# CAN_USB_DISPLAY.net
KiCad netlist of a schematic drawn in Altium Designer
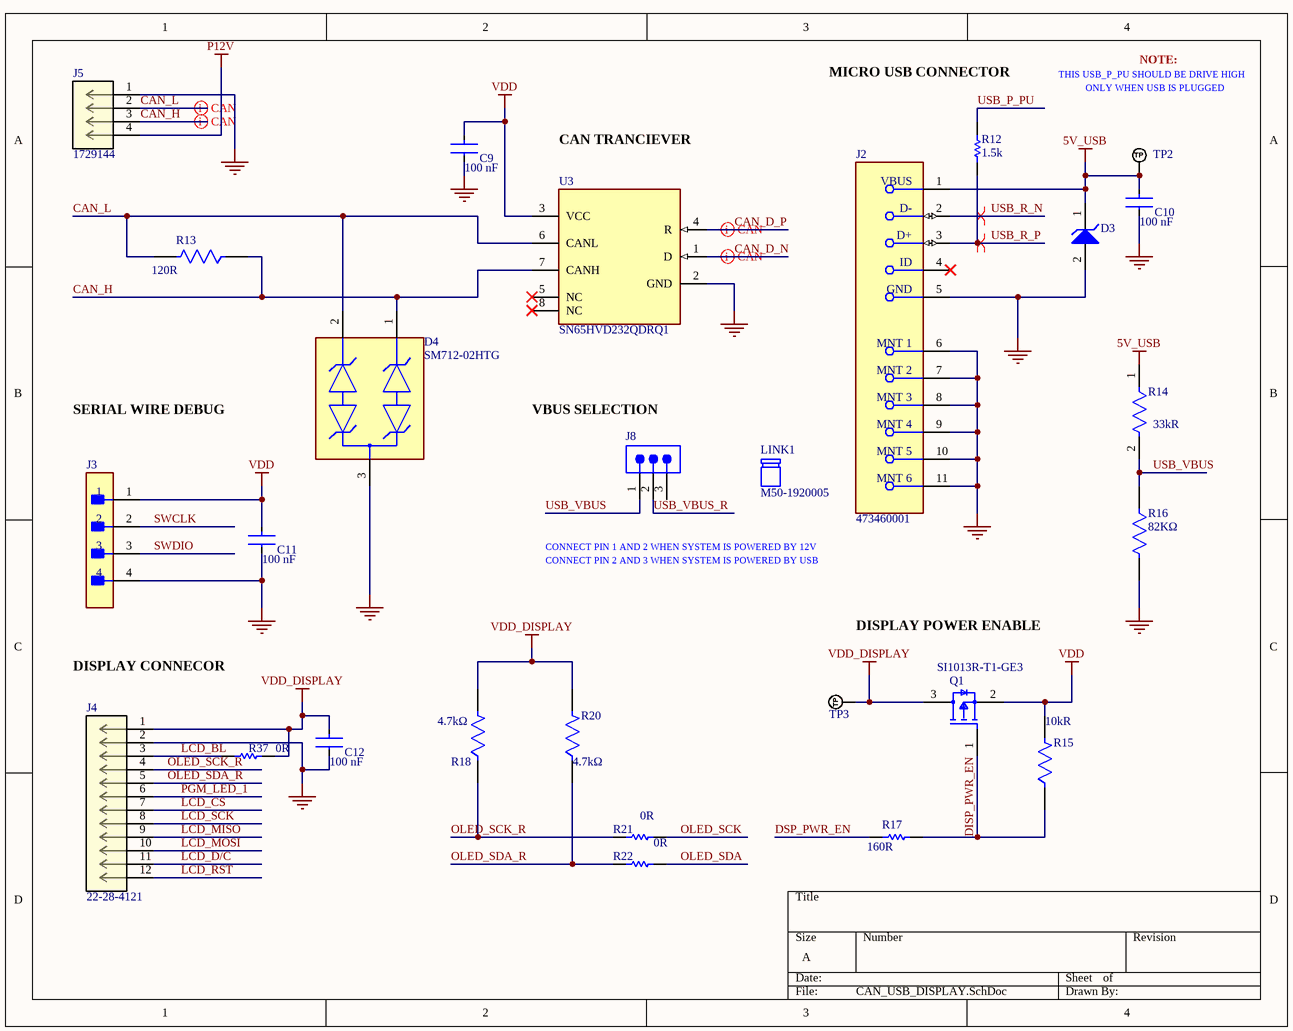
[diagram p0: CAN_USB_DISPLAY.SchDoc]

(export (version "E")
  (design (tool "Eeschema 10.0.6"))
  (components
    (comp (ref "C9")
      (value "CC0402KRX7R7BB104")
      (footprint "FP-CC0402-MFG")
      (description "CAP CER 0.1UF 16V X7R 0402")
      (fields
        (field (name "CAPACITANCE") "100 nF")
        (field (name "MANUFACTURER") "YAGEO")
        (field (name "TOLERANCE") "0.1")
      )
      (libsource (lib "Altium Content Vault") (part "11868f565c42a9108669ba33697ecf6"))
    )
    (comp (ref "C10")
      (value "CC0402KRX7R7BB104")
      (footprint "FP-CC0402-MFG")
      (description "CAP CER 0.1UF 16V X7R 0402")
      (fields
        (field (name "CAPACITANCE") "100 nF")
        (field (name "MANUFACTURER") "YAGEO")
        (field (name "TOLERANCE") "0.1")
      )
      (libsource (lib "Altium Content Vault") (part "11868f565c42a9108669ba33697ecf6"))
    )
    (comp (ref "C11")
      (value "CC0402KRX7R7BB104")
      (footprint "FP-CC0402-MFG")
      (description "CAP CER 0.1UF 16V X7R 0402")
      (fields
        (field (name "CAPACITANCE") "100 nF")
        (field (name "MANUFACTURER") "YAGEO")
        (field (name "TOLERANCE") "0.1")
      )
      (libsource (lib "Altium Content Vault") (part "11868f565c42a9108669ba33697ecf6"))
    )
    (comp (ref "C12")
      (value "CC0402KRX7R7BB104")
      (footprint "FP-CC0402-MFG")
      (description "CAP CER 0.1UF 16V X7R 0402")
      (fields
        (field (name "CAPACITANCE") "100 nF")
        (field (name "MANUFACTURER") "YAGEO")
        (field (name "TOLERANCE") "0.1")
      )
      (libsource (lib "Altium Content Vault") (part "11868f565c42a9108669ba33697ecf6"))
    )
    (comp (ref "D3")
      (value "ESD5Z5.0T1G")
      (footprint "ONSC-SOD-523-2-502-01_V")
      (fields (field (name "MANUFACTURER") "On Semiconductor"))
      (libsource (lib "Altium Content Vault") (part "ONSC-K1A2-2"))
    )
    (comp (ref "D4")
      (value "SM712-02HTG")
      (footprint "FP-SM712-MFG")
      (description "TVS DIODE 12V 31V SOT23-3")
      (libsource (lib "Altium Content Vault") (part "30adef48d791aa94530531f6d7a3f92"))
    )
    (comp (ref "J2")
      (value "473460001")
      (footprint "FP-473460001-MFG")
      (description "CONN RCPT USB2.0 MICRO B SMD R/A")
      (fields
        (field (name "OCTOPART") "https://octopart.com/47346-0001-molex-7164928")
        (field (name "MANUFACTURER") "Molex")
      )
      (libsource (lib "Altium Content Vault") (part "53ae1f1d9b557310b43ca686e5bb76a"))
    )
    (comp (ref "J3")
      (value "HTSW-104-07-G-S")
      (footprint "FP-HTSW-104-07-G-S-MFG")
      (description "CONN HEADER VERT 4POS 2.54MM")
      (libsource (lib "Altium Content Vault") (part "299a8cea1bdcbc3624fe62c390fa72c"))
    )
    (comp (ref "J4")
      (value "22-28-4121")
      (footprint "12 POS_2.54MM_MOLEX")
      (description "KK 254 Breakaway Header, Vertical, 12 Circuits, Tin (Sn) Plating, Mating Pin Length 8.13mm")
      (fields (field (name "MANUFACTURER") "Molex"))
      (libsource (lib "F1_MODULE") (part "22-28-4121"))
    )
    (comp (ref "J5")
      (value "1729144")
      (footprint "PHOENIX_1729144")
      (description "Block, Terminal; 13.5 A; 250 V; 5.08 mm; 26 to 16 AWG; 4; Screw; Solder; 4 kV")
      (fields (field (name "MANUFACTURER") "Phoenix Contact") (field (name "VOLTAGE") "300V"))
      (libsource (lib "F1_MODULE") (part "1729144"))
    )
    (comp (ref "J8")
      (value "61300311121")
      (footprint "61300311121")
      (description "CONN HEADER VERT 3POS 2.54MM")
      (libsource (lib "Altium Content Vault") (part "Header_Male_1R_03P"))
    )
    (comp (ref "LINK1")
      (value "M50-1920005")
      (description "CONN SHUNT 1.27MM RED")
      (fields (field (name "MANUFACTURER") "Harwin") (field (name "LCSC PART NUMBER") "C6985646"))
      (libsource (lib "Schlib") (part "M50-1920005"))
    )
    (comp (ref "Q1")
      (value "SI1013R-T1-GE3")
      (footprint "FP-C15-1445-MFG")
      (description "MOSFET P-CH 20V 350MA SC75A")
      (libsource (lib "Altium Content Vault") (part "274ba75a4227b453460520a6808ef61"))
    )
    (comp (ref "R12")
      (value "ERA2AEB152X")
      (footprint "RESC1005X40X25LL10T10")
      (description "RES SMD 1.5K OHM 0.1% 1/16W 0402")
      (fields (field (name "MANUFACTURER") "Panasonic") (field (name "RESISTANCE") "1.5k"))
      (libsource (lib "Altium Content Vault") (part "RES"))
    )
    (comp (ref "R13")
      (value "RMCF1206FTR120")
      (footprint "FP-RMCF1206-MFG")
      (description "0.12Ω ±1% 0.25W 1206 Thick Film Chip Resistor AEC-Q200 compliant")
      (fields (field (name "TOLERANCE") "1%") (field (name "RESISTANCE") "120R"))
      (libsource (lib "Altium Content Vault") (part "1029c3af85768c4190bb7ad29bc67b5"))
    )
    (comp (ref "R14")
      (value "ERA-2AEB333X")
      (footprint "FP-ERA2A-MFG")
      (description "RES SMD 33K OHM 0.1% 1/16W 0402")
      (fields (field (name "TOLERANCE") "0.1%") (field (name "RESISTANCE") "33kR"))
      (libsource (lib "") (part "1029c3af85768c4190bb7ad29bc67b5_1"))
    )
    (comp (ref "R15")
      (value "RC0402JR-0710KL")
      (footprint "FP-RC0402-0_4-MFG")
      (description "RES 10K OHM 5% 1/16W 0402")
      (fields (field (name "RESISTANCE") "10kR") (field (name "TOLERANCE") "5%"))
      (libsource (lib "Altium Content Vault") (part "1029c3af85768c4190bb7ad29bc67b5"))
    )
    (comp (ref "R16")
      (value "CRGCQ0402F82K")
      (footprint "FP-CRGCQ0402-IPC_C")
      (description "CRGCQ0402 82KΩ 1% ±100ppm/°C 50V")
      (fields
        (field (name "MANUFACTURER") "TE Connectivity")
        (field (name "OCTOPART") "https://octopart.com/crgcq0402f82k-te+connectivity-91017988")
        (field (name "RESISTANCE") "82KΩ")
      )
      (libsource (lib "Altium Content Vault") (part "1029c3af85768c4190bb7ad29bc67b5"))
    )
    (comp (ref "R17")
      (value "ERJ-2GEJ161X")
      (footprint "RESC1005X40X25NL05T05")
      (fields (field (name "MANUFACTURER") "Panasonic") (field (name "RESISTANCE") "160R"))
      (libsource (lib "Altium Content Vault") (part "RES"))
    )
    (comp (ref "R18")
      (value "RC0402JR-074K7L")
      (footprint "FP-RC0402-0_4-MFG")
      (description "4.7 kOhms ±5% 0.063W, 1/16W Chip Resistor 0402 (1005 Metric) Moisture Resistant Thick Film")
      (fields (field (name "TOLERANCE") "5%") (field (name "RESISTANCE") "4.7kΩ"))
      (libsource (lib "Altium Content Vault") (part "RC0402JR-074K7L"))
    )
    (comp (ref "R20")
      (value "RC0402JR-074K7L")
      (footprint "FP-RC0402-0_4-MFG")
      (description "4.7 kOhms ±5% 0.063W, 1/16W Chip Resistor 0402 (1005 Metric) Moisture Resistant Thick Film")
      (fields (field (name "TOLERANCE") "5%") (field (name "RESISTANCE") "4.7kΩ"))
      (libsource (lib "Altium Content Vault") (part "RC0402JR-074K7L"))
    )
    (comp (ref "R21")
      (value "ERJ2GE0R00X")
      (footprint "RESC1005X40X25LL05T05")
      (description "Chip Resistor, 0 Ohm, 0.1 W, -55 to 155 degC, 0402 (1005 Metric), RoHS, Tape and Reel")
      (fields
        (field (name "MANUFACTURER") "Panasonic")
        (field (name "RESISTANCE") "0R")
        (field (name "TOLERANCE") "5%")
      )
      (libsource (lib "Altium Content Vault") (part "RES-2"))
    )
    (comp (ref "R22")
      (value "ERJ2GE0R00X")
      (footprint "RESC1005X40X25LL05T05")
      (description "Chip Resistor, 0 Ohm, 0.1 W, -55 to 155 degC, 0402 (1005 Metric), RoHS, Tape and Reel")
      (fields
        (field (name "MANUFACTURER") "Panasonic")
        (field (name "RESISTANCE") "0R")
        (field (name "TOLERANCE") "5%")
      )
      (libsource (lib "Altium Content Vault") (part "RES-2"))
    )
    (comp (ref "R37")
      (value "ERJ2GE0R00X")
      (footprint "RESC1005X40X25LL05T05")
      (description "Chip Resistor, 0 Ohm, 0.1 W, -55 to 155 degC, 0402 (1005 Metric), RoHS, Tape and Reel")
      (fields
        (field (name "MANUFACTURER") "Panasonic")
        (field (name "RESISTANCE") "0R")
        (field (name "TOLERANCE") "5%")
      )
      (libsource (lib "Altium Content Vault") (part "RES-2"))
    )
    (comp (ref "TP2")
      (value "TP_NOBOM")
      (footprint "PAD_RND_1MM")
      (description "Test Point Round 1mm (NO BOM)")
      (libsource (lib "Schematic-Lib-PhilsLab") (part "TEST_POINT_RND_1MM"))
    )
    (comp (ref "TP3")
      (value "TP_NOBOM")
      (footprint "PAD_RND_1MM")
      (description "Test Point Round 1mm (NO BOM)")
      (libsource (lib "Schematic-Lib-PhilsLab") (part "TEST_POINT_RND_1MM"))
    )
    (comp (ref "U3")
      (value "SN65HVD232QDRQ1")
      (footprint "CAN IC")
      (description "Texas Instruments - SN65HVD232QDRQ1 - Can Bus, Transceiver, Can, 1, 1, 3 V, 3.6 V, SOIC")
      (fields (field (name "MANUFACTURER") "Texas Instruments"))
      (libsource (lib "F1_MODULE") (part "SN65HVD232QDRQ1"))
    )
  )
  (nets
    (net (code "1") (name "/CAN_D_N") (class "Default")
      (node (ref "U3") (pin "1") (pinfunction "D_1") (pintype "input"))
    )
    (net (code "2") (name "/CAN_D_P") (class "Default")
      (node (ref "U3") (pin "4") (pinfunction "R_4") (pintype "input"))
    )
    (net (code "3") (name "/CAN_H") (class "Default")
      (node (ref "D4") (pin "1") (pinfunction "1_1") (pintype "passive"))
      (node (ref "J5") (pin "3") (pinfunction "3_3") (pintype "passive"))
      (node (ref "R13") (pin "1") (pinfunction "1_1") (pintype "passive"))
      (node (ref "U3") (pin "7") (pinfunction "CANH_7") (pintype "passive"))
    )
    (net (code "4") (name "/CAN_L") (class "Default")
      (node (ref "D4") (pin "2") (pinfunction "2_2") (pintype "passive"))
      (node (ref "J5") (pin "2") (pinfunction "2_2") (pintype "passive"))
      (node (ref "R13") (pin "2") (pinfunction "2_2") (pintype "passive"))
      (node (ref "U3") (pin "6") (pinfunction "CANL_6") (pintype "passive"))
    )
    (net (code "5") (name "/DISP_PWR_EN") (class "Default")
      (node (ref "Q1") (pin "1") (pinfunction "G_1") (pintype "passive"))
      (node (ref "R15") (pin "1") (pinfunction "1_1") (pintype "passive"))
      (node (ref "R17") (pin "2") (pinfunction "2_2") (pintype "passive"))
    )
    (net (code "6") (name "/DSP_PWR_EN") (class "Default")
      (node (ref "R17") (pin "1") (pinfunction "1_1") (pintype "passive"))
    )
    (net (code "7") (name "/LCD_BL") (class "Default")
      (node (ref "J4") (pin "3") (pinfunction "3_3") (pintype "passive"))
      (node (ref "R37") (pin "1") (pinfunction "1_1") (pintype "passive"))
    )
    (net (code "8") (name "/LCD_CS") (class "Default")
      (node (ref "J4") (pin "7") (pinfunction "7_7") (pintype "passive"))
    )
    (net (code "9") (name "/LCD_D{slash}C") (class "Default")
      (node (ref "J4") (pin "11") (pinfunction "11_11") (pintype "passive"))
    )
    (net (code "10") (name "/LCD_MISO") (class "Default")
      (node (ref "J4") (pin "9") (pinfunction "9_9") (pintype "passive"))
    )
    (net (code "11") (name "/LCD_MOSI") (class "Default")
      (node (ref "J4") (pin "10") (pinfunction "10_10") (pintype "passive"))
    )
    (net (code "12") (name "/LCD_RST") (class "Default")
      (node (ref "J4") (pin "12") (pinfunction "12_12") (pintype "passive"))
    )
    (net (code "13") (name "/LCD_SCK") (class "Default")
      (node (ref "J4") (pin "8") (pinfunction "8_8") (pintype "passive"))
    )
    (net (code "14") (name "/OLED_SCK") (class "Default")
      (node (ref "R21") (pin "2") (pinfunction "2_2") (pintype "passive"))
    )
    (net (code "15") (name "/OLED_SCK_R") (class "Default")
      (node (ref "J4") (pin "4") (pinfunction "4_4") (pintype "passive"))
      (node (ref "R18") (pin "1") (pinfunction "1_1") (pintype "passive"))
      (node (ref "R21") (pin "1") (pinfunction "1_1") (pintype "passive"))
    )
    (net (code "16") (name "/OLED_SDA") (class "Default")
      (node (ref "R22") (pin "2") (pinfunction "2_2") (pintype "passive"))
    )
    (net (code "17") (name "/OLED_SDA_R") (class "Default")
      (node (ref "J4") (pin "5") (pinfunction "5_5") (pintype "passive"))
      (node (ref "R20") (pin "1") (pinfunction "1_1") (pintype "passive"))
      (node (ref "R22") (pin "1") (pinfunction "1_1") (pintype "passive"))
    )
    (net (code "18") (name "/PGM_LED_1") (class "Default")
      (node (ref "J4") (pin "6") (pinfunction "6_6") (pintype "passive"))
    )
    (net (code "19") (name "/SWCLK") (class "Default")
      (node (ref "J3") (pin "2") (pinfunction "2_2") (pintype "passive"))
    )
    (net (code "20") (name "/SWDIO") (class "Default")
      (node (ref "J3") (pin "3") (pinfunction "3_3") (pintype "passive"))
    )
    (net (code "21") (name "/USB_P_PU") (class "Default")
      (node (ref "R12") (pin "2") (pinfunction "2_2") (pintype "passive"))
    )
    (net (code "22") (name "/USB_R_N") (class "Default")
      (node (ref "J2") (pin "2") (pinfunction "D-_2") (pintype "bidirectional"))
    )
    (net (code "23") (name "/USB_R_P") (class "Default")
      (node (ref "J2") (pin "3") (pinfunction "D+_3") (pintype "bidirectional"))
      (node (ref "R12") (pin "1") (pinfunction "1_1") (pintype "passive"))
    )
    (net (code "24") (name "/USB_VBUS") (class "Default")
      (node (ref "J8") (pin "1") (pinfunction "1_1") (pintype "passive"))
      (node (ref "R14") (pin "2") (pinfunction "2_2") (pintype "passive"))
      (node (ref "R16") (pin "1") (pinfunction "1_1") (pintype "passive"))
    )
    (net (code "25") (name "/USB_VBUS_R") (class "Default")
      (node (ref "J8") (pin "2") (pinfunction "2_2") (pintype "passive"))
    )
    (net (code "26") (name "5V_USB") (class "Default")
      (node (ref "C10") (pin "1") (pinfunction "1_1") (pintype "passive"))
      (node (ref "D3") (pin "1") (pinfunction "K_1") (pintype "passive"))
      (node (ref "J2") (pin "1") (pinfunction "VBUS_1") (pintype "power_in"))
      (node (ref "R14") (pin "1") (pinfunction "1_1") (pintype "passive"))
      (node (ref "TP2") (pin "1") (pinfunction "TP_1") (pintype "passive"))
    )
    (net (code "27") (name "GND") (class "Default")
      (node (ref "C10") (pin "2") (pinfunction "2_2") (pintype "passive"))
      (node (ref "C11") (pin "2") (pinfunction "2_2") (pintype "passive"))
      (node (ref "C12") (pin "2") (pinfunction "2_2") (pintype "passive"))
      (node (ref "C9") (pin "2") (pinfunction "2_2") (pintype "passive"))
      (node (ref "D3") (pin "2") (pinfunction "A_2") (pintype "passive"))
      (node (ref "D4") (pin "3") (pinfunction "3_3") (pintype "passive"))
      (node (ref "J2") (pin "10") (pinfunction "MNT_5_10") (pintype "passive"))
      (node (ref "J2") (pin "11") (pinfunction "MNT_6_11") (pintype "passive"))
      (node (ref "J2") (pin "5") (pinfunction "GND_5") (pintype "power_in"))
      (node (ref "J2") (pin "6") (pinfunction "MNT_1_6") (pintype "passive"))
      (node (ref "J2") (pin "7") (pinfunction "MNT_2_7") (pintype "passive"))
      (node (ref "J2") (pin "8") (pinfunction "MNT_3_8") (pintype "passive"))
      (node (ref "J2") (pin "9") (pinfunction "MNT_4_9") (pintype "passive"))
      (node (ref "J3") (pin "4") (pinfunction "4_4") (pintype "passive"))
      (node (ref "J4") (pin "2") (pinfunction "2_2") (pintype "passive"))
      (node (ref "J5") (pin "1") (pinfunction "1_1") (pintype "passive"))
      (node (ref "R16") (pin "2") (pinfunction "2_2") (pintype "passive"))
      (node (ref "U3") (pin "2") (pinfunction "GND_2") (pintype "power_in"))
    )
    (net (code "28") (name "P12V") (class "Default")
      (node (ref "J5") (pin "4") (pinfunction "4_4") (pintype "passive"))
    )
    (net (code "29") (name "VDD") (class "Default")
      (node (ref "C11") (pin "1") (pinfunction "1_1") (pintype "passive"))
      (node (ref "C9") (pin "1") (pinfunction "1_1") (pintype "passive"))
      (node (ref "J3") (pin "1") (pinfunction "1_1") (pintype "passive"))
      (node (ref "Q1") (pin "2") (pinfunction "S_2") (pintype "passive"))
      (node (ref "R15") (pin "2") (pinfunction "2_2") (pintype "passive"))
      (node (ref "U3") (pin "3") (pinfunction "VCC_3") (pintype "power_in"))
    )
    (net (code "30") (name "VDD_DISPLAY") (class "Default")
      (node (ref "C12") (pin "1") (pinfunction "1_1") (pintype "passive"))
      (node (ref "J4") (pin "1") (pinfunction "1_1") (pintype "passive"))
      (node (ref "Q1") (pin "3") (pinfunction "D_3") (pintype "passive"))
      (node (ref "R18") (pin "2") (pinfunction "2_2") (pintype "passive"))
      (node (ref "R20") (pin "2") (pinfunction "2_2") (pintype "passive"))
      (node (ref "R37") (pin "2") (pinfunction "2_2") (pintype "passive"))
      (node (ref "TP3") (pin "1") (pinfunction "TP_1") (pintype "passive"))
    )
    (net (code "31") (name "unconnected-(J2-ID-Pad4)") (class "Default")
      (node (ref "J2") (pin "4") (pinfunction "ID_4") (pintype "passive+no_connect"))
    )
    (net (code "32") (name "unconnected-(J8-Pad3)") (class "Default")
      (node (ref "J8") (pin "3") (pinfunction "3_3") (pintype "passive"))
    )
    (net (code "33") (name "unconnected-(U3-NC-Pad5)") (class "Default")
      (node (ref "U3") (pin "5") (pinfunction "NC_5") (pintype "passive+no_connect"))
    )
    (net (code "34") (name "unconnected-(U3-NC-Pad8)") (class "Default")
      (node (ref "U3") (pin "8") (pinfunction "NC_8") (pintype "passive+no_connect"))
    )
  )
)
